# 1sVoltageMonitor.net
KiCad netlist of a schematic drawn in Altium Designer
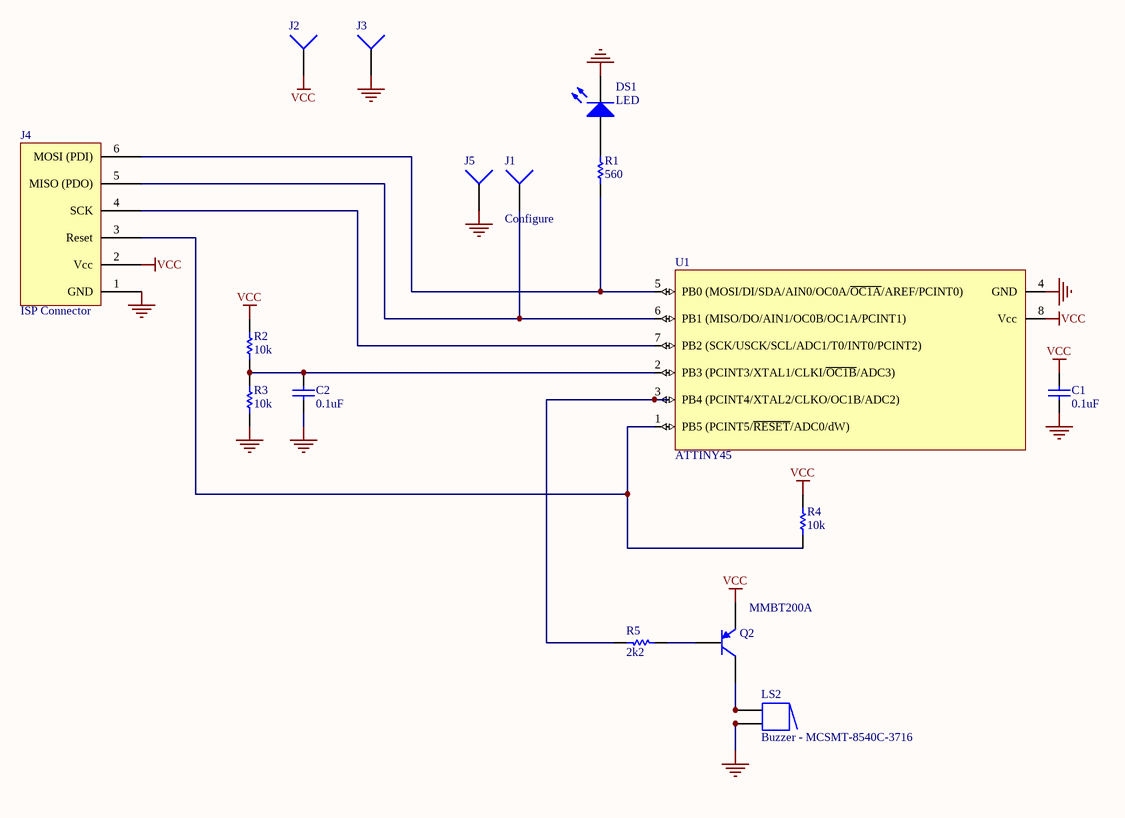
[diagram p0: 1sVoltageMonitor.SchDoc]

(export (version "E")
  (design (tool "Eeschema 10.0.6"))
  (components
    (comp (ref "C1")
      (value "0.1uF")
      (footprint "Cap SMD 0603")
      (description "Capacitor")
      (fields (field (name "Comment") "Cap") (field (name "PUBLISHER") "Altium Limited"))
      (libsource (lib "Custom") (part "Cap"))
    )
    (comp (ref "C2")
      (value "0.1uF")
      (footprint "Cap SMD 0603")
      (description "Capacitor")
      (fields (field (name "Comment") "Cap") (field (name "PUBLISHER") "Altium Limited"))
      (libsource (lib "Custom") (part "Cap"))
    )
    (comp (ref "DS1")
      (value "LED")
      (footprint "LED SMD 0603")
      (description "RGB LED Common Anode")
      (fields (field (name "PUBLISHER") "Altium Limited"))
      (libsource (lib "Custom") (part "LED"))
    )
    (comp (ref "J1")
      (value "Configure")
      (footprint "PIN1")
      (description "Socket")
      (fields (field (name "PUBLISHER") "Altium Limited"))
      (libsource (lib "Miscellaneous Connectors") (part "Socket"))
    )
    (comp (ref "J2")
      (value "~")
      (footprint "PIN1")
      (description "Socket")
      (fields (field (name "PUBLISHER") "Altium Limited"))
      (libsource (lib "Miscellaneous Connectors") (part "Socket"))
    )
    (comp (ref "J3")
      (value "~")
      (footprint "PIN1")
      (description "Socket")
      (fields (field (name "PUBLISHER") "Altium Limited"))
      (libsource (lib "Miscellaneous Connectors") (part "Socket"))
    )
    (comp (ref "J4")
      (value "ISP Connector")
      (footprint "Miscellaneous Connector PCB:HDR2X3")
      (libsource (lib "Custom") (part "ISP Connector"))
    )
    (comp (ref "J5")
      (value "~")
      (footprint "PIN1")
      (description "Socket")
      (fields (field (name "PUBLISHER") "Altium Limited"))
      (libsource (lib "Miscellaneous Connectors") (part "Socket"))
    )
    (comp (ref "LS2")
      (value "Buzzer - MCSMT-8540C-3716")
      (footprint "Buzzer MCSMT-8540C-3716")
      (description "MCSMT-8540C-3716")
      (fields (field (name "PUBLISHER") "Altium Limited"))
      (libsource (lib "Miscellaneous Devices") (part "Buzzer"))
    )
    (comp (ref "Q2")
      (value "MMBT200A")
      (footprint "SO-G3")
      (description "General Purpose Amplifier NPN Silicon")
      (fields (field (name "PUBLISHER") "Altium Limited"))
      (libsource (lib "Custom") (part "MMBT200A"))
    )
    (comp (ref "R1")
      (value "560")
      (footprint "Res SMD 0603")
      (fields (field (name "Comment") "Res1"))
      (libsource (lib "Custom") (part "Resistor"))
    )
    (comp (ref "R2")
      (value "10k")
      (footprint "Res SMD 0603")
      (fields (field (name "Comment") "Res1"))
      (libsource (lib "Custom") (part "Resistor"))
    )
    (comp (ref "R3")
      (value "10k")
      (footprint "Res SMD 0603")
      (fields (field (name "Comment") "Res1"))
      (libsource (lib "Custom") (part "Resistor"))
    )
    (comp (ref "R4")
      (value "10k")
      (footprint "Res SMD 0603")
      (fields (field (name "Comment") "Res1"))
      (libsource (lib "Custom") (part "Resistor"))
    )
    (comp (ref "R5")
      (value "2k2")
      (footprint "Res SMD 0603")
      (fields (field (name "Comment") "Res1"))
      (libsource (lib "Custom") (part "Resistor"))
    )
    (comp (ref "U1")
      (value "ATTINY45")
      (footprint "TSSOP8-4.4mm")
      (libsource (lib "Custom") (part "ATTINY45"))
    )
  )
  (nets
    (net (code "1") (name "GND") (class "Default")
      (node (ref "C1") (pin "1") (pinfunction "1_1") (pintype "passive"))
      (node (ref "C2") (pin "1") (pinfunction "1_1") (pintype "passive"))
      (node (ref "DS1") (pin "K") (pinfunction "K_K") (pintype "passive"))
      (node (ref "J3") (pin "1") (pinfunction "1_1") (pintype "passive"))
      (node (ref "J4") (pin "1") (pinfunction "GND_1") (pintype "passive"))
      (node (ref "J5") (pin "1") (pinfunction "1_1") (pintype "passive"))
      (node (ref "LS2") (pin "2") (pinfunction "2_2") (pintype "passive"))
      (node (ref "LS2") (pin "2A") (pinfunction "2A_2A") (pintype "passive"))
      (node (ref "R3") (pin "1") (pinfunction "1_1") (pintype "passive"))
      (node (ref "U1") (pin "4") (pinfunction "GND_4") (pintype "power_in"))
    )
    (net (code "2") (name "Net-(DS1-PadA)") (class "Default")
      (node (ref "DS1") (pin "A") (pinfunction "A_A") (pintype "passive"))
      (node (ref "R1") (pin "1") (pinfunction "1_1") (pintype "passive"))
    )
    (net (code "3") (name "Net-(J4-MISO_(PDO))") (class "Default")
      (node (ref "J1") (pin "1") (pinfunction "1_1") (pintype "passive"))
      (node (ref "J4") (pin "5") (pinfunction "MISO_(PDO)_5") (pintype "passive"))
      (node (ref "U1") (pin "6") (pinfunction "PB1_(MISO/DO/AIN1/OC0B/OC1A/PCINT1)_6") (pintype "bidirectional"))
    )
    (net (code "4") (name "Net-(J4-MOSI_(PDI))") (class "Default")
      (node (ref "J4") (pin "6") (pinfunction "MOSI_(PDI)_6") (pintype "passive"))
      (node (ref "R1") (pin "2") (pinfunction "2_2") (pintype "passive"))
      (node (ref "U1") (pin "5") (pinfunction "PB0_(MOSI/DI/SDA/AIN0/OC0A/~{OC1A}/AREF/PCINT0)_5") (pintype "bidirectional"))
    )
    (net (code "5") (name "Net-(J4-Reset)") (class "Default")
      (node (ref "J4") (pin "3") (pinfunction "Reset_3") (pintype "passive"))
      (node (ref "R4") (pin "1") (pinfunction "1_1") (pintype "passive"))
      (node (ref "U1") (pin "1") (pinfunction "PB5_(PCINT5/~{RESET}/ADC0/dW)_1") (pintype "bidirectional"))
    )
    (net (code "6") (name "Net-(J4-SCK)") (class "Default")
      (node (ref "J4") (pin "4") (pinfunction "SCK_4") (pintype "passive"))
      (node (ref "U1") (pin "7") (pinfunction "PB2_(SCK/USCK/SCL/ADC1/T0/INT0/PCINT2)_7") (pintype "bidirectional"))
    )
    (net (code "7") (name "Net-(LS2-Pad1)") (class "Default")
      (node (ref "LS2") (pin "1") (pinfunction "1_1") (pintype "passive"))
      (node (ref "LS2") (pin "1A") (pinfunction "1A_1A") (pintype "passive"))
      (node (ref "Q2") (pin "C") (pinfunction "C_C") (pintype "passive"))
    )
    (net (code "8") (name "Net-(Q2-PadB)") (class "Default")
      (node (ref "Q2") (pin "B") (pinfunction "B_B") (pintype "passive"))
      (node (ref "R5") (pin "1") (pinfunction "1_1") (pintype "passive"))
    )
    (net (code "9") (name "Net-(U1-PB3_(PCINT3{slash}XTAL1{slash}CLKI{slash}~{OC1B}{slash}ADC3))") (class "Default")
      (node (ref "C2") (pin "2") (pinfunction "2_2") (pintype "passive"))
      (node (ref "R2") (pin "1") (pinfunction "1_1") (pintype "passive"))
      (node (ref "R3") (pin "2") (pinfunction "2_2") (pintype "passive"))
      (node (ref "U1") (pin "2") (pinfunction "PB3_(PCINT3/XTAL1/CLKI/~{OC1B}/ADC3)_2") (pintype "bidirectional"))
    )
    (net (code "10") (name "Net-(U1-PB4_(PCINT4{slash}XTAL2{slash}CLKO{slash}OC1B{slash}ADC2))") (class "Default")
      (node (ref "R5") (pin "2") (pinfunction "2_2") (pintype "passive"))
      (node (ref "U1") (pin "3") (pinfunction "PB4_(PCINT4/XTAL2/CLKO/OC1B/ADC2)_3") (pintype "bidirectional"))
    )
    (net (code "11") (name "VCC") (class "Default")
      (node (ref "C1") (pin "2") (pinfunction "2_2") (pintype "passive"))
      (node (ref "J2") (pin "1") (pinfunction "1_1") (pintype "passive"))
      (node (ref "J4") (pin "2") (pinfunction "Vcc_2") (pintype "passive"))
      (node (ref "Q2") (pin "E") (pinfunction "E_E") (pintype "passive"))
      (node (ref "R2") (pin "2") (pinfunction "2_2") (pintype "passive"))
      (node (ref "R4") (pin "2") (pinfunction "2_2") (pintype "passive"))
      (node (ref "U1") (pin "8") (pinfunction "Vcc_8") (pintype "power_in"))
    )
  )
)
